# TrainTracker_V01.net
KiCad netlist of a schematic drawn in EAGLE
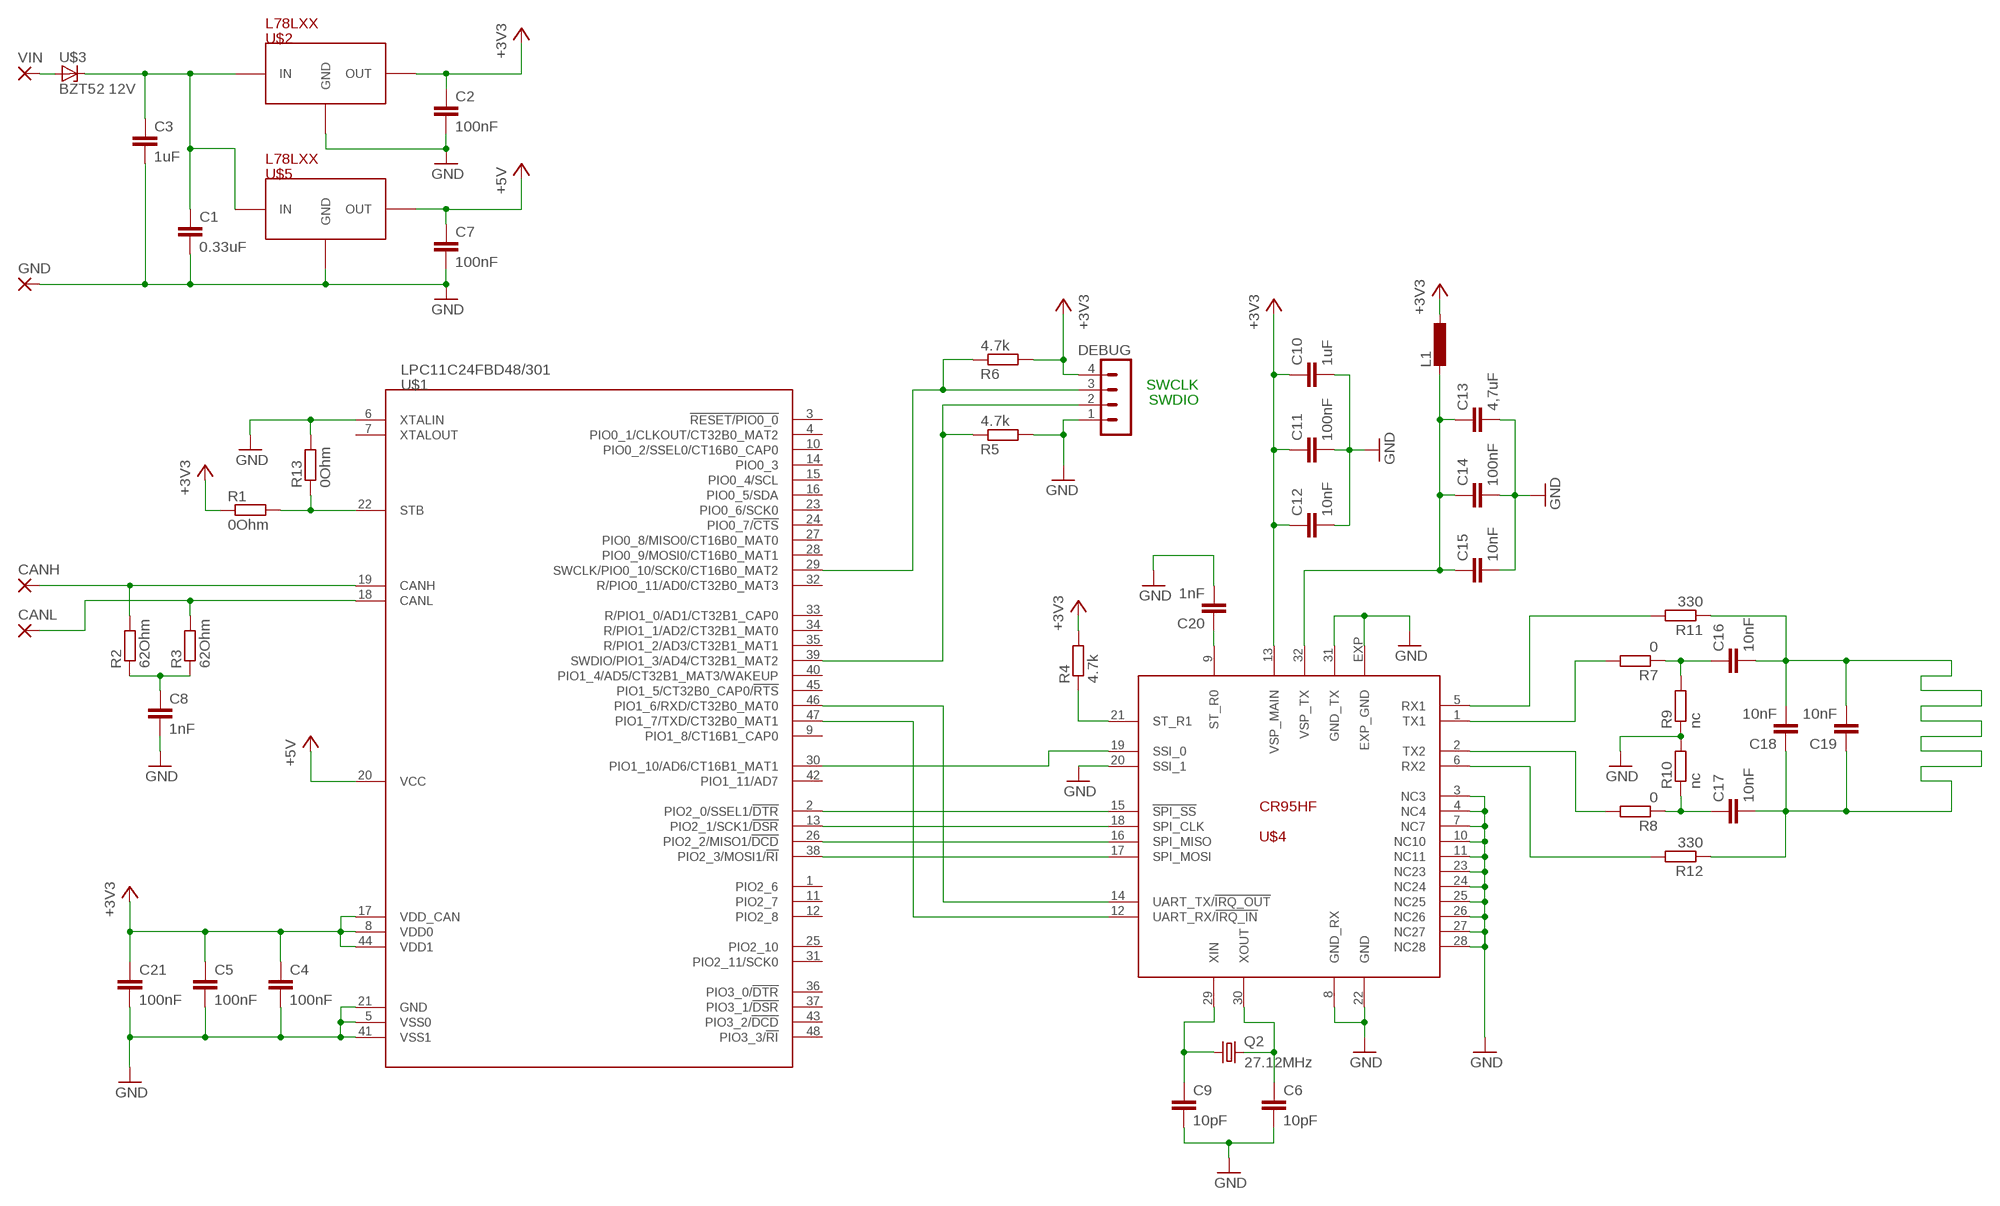
[diagram p0: schematic, sheet 1]

(export (version "E")
  (design (tool "Eeschema 10.0.6"))
  (components
    (comp (ref "C1")
      (value "0.33uF")
      (footprint "eagle-import:C0402")
      (libsource (lib "eagle-import") (part "C-EUC0402"))
    )
    (comp (ref "C2")
      (value "100nF")
      (footprint "eagle-import:C0402")
      (libsource (lib "eagle-import") (part "C-EUC0402"))
    )
    (comp (ref "C3")
      (value "1uF")
      (footprint "eagle-import:C0603K")
      (libsource (lib "eagle-import") (part "C-EUC0603K"))
    )
    (comp (ref "C4")
      (value "100nF")
      (footprint "eagle-import:C0402")
      (libsource (lib "eagle-import") (part "C-EUC0402"))
    )
    (comp (ref "C5")
      (value "100nF")
      (footprint "eagle-import:C0402")
      (libsource (lib "eagle-import") (part "C-EUC0402"))
    )
    (comp (ref "C6")
      (value "10pF")
      (footprint "eagle-import:C0402")
      (libsource (lib "eagle-import") (part "C-EUC0402"))
    )
    (comp (ref "C7")
      (value "100nF")
      (footprint "eagle-import:C0402")
      (libsource (lib "eagle-import") (part "C-EUC0402"))
    )
    (comp (ref "C8")
      (value "1nF")
      (footprint "eagle-import:C0402")
      (libsource (lib "eagle-import") (part "C-EUC0402"))
    )
    (comp (ref "C9")
      (value "10pF")
      (footprint "eagle-import:C0402")
      (libsource (lib "eagle-import") (part "C-EUC0402"))
    )
    (comp (ref "C10")
      (value "1uF")
      (footprint "eagle-import:C0603K")
      (libsource (lib "eagle-import") (part "C-EUC0603K"))
    )
    (comp (ref "C11")
      (value "100nF")
      (footprint "eagle-import:C0402")
      (libsource (lib "eagle-import") (part "C-EUC0402"))
    )
    (comp (ref "C12")
      (value "10nF")
      (footprint "eagle-import:C0402")
      (libsource (lib "eagle-import") (part "C-EUC0402"))
    )
    (comp (ref "C13")
      (value "4,7uF")
      (footprint "eagle-import:C0603K")
      (libsource (lib "eagle-import") (part "C-EUC0603K"))
    )
    (comp (ref "C14")
      (value "100nF")
      (footprint "eagle-import:C0402")
      (libsource (lib "eagle-import") (part "C-EUC0402"))
    )
    (comp (ref "C15")
      (value "10nF")
      (footprint "eagle-import:C0402")
      (libsource (lib "eagle-import") (part "C-EUC0402"))
    )
    (comp (ref "C16")
      (value "10nF")
      (footprint "eagle-import:C0402")
      (libsource (lib "eagle-import") (part "C-EUC0402"))
    )
    (comp (ref "C17")
      (value "10nF")
      (footprint "eagle-import:C0402")
      (libsource (lib "eagle-import") (part "C-EUC0402"))
    )
    (comp (ref "C18")
      (value "10nF")
      (footprint "eagle-import:C0402")
      (libsource (lib "eagle-import") (part "C-EUC0402"))
    )
    (comp (ref "C19")
      (value "10nF")
      (footprint "eagle-import:C0402")
      (libsource (lib "eagle-import") (part "C-EUC0402"))
    )
    (comp (ref "C20")
      (value "1nF")
      (footprint "eagle-import:C0402")
      (libsource (lib "eagle-import") (part "C-EUC0402"))
    )
    (comp (ref "C21")
      (value "100nF")
      (footprint "eagle-import:C0402")
      (libsource (lib "eagle-import") (part "C-EUC0402"))
    )
    (comp (ref "CANH")
      (value "SMD5")
      (footprint "eagle-import:SMD2,54-5,08")
      (libsource (lib "eagle-import") (part "SMD5"))
    )
    (comp (ref "CANL")
      (value "SMD5")
      (footprint "eagle-import:SMD2,54-5,08")
      (libsource (lib "eagle-import") (part "SMD5"))
    )
    (comp (ref "DEBUG")
      (value "MA04-1")
      (footprint "eagle-import:MA04-1")
      (libsource (lib "eagle-import") (part "MA04-1"))
    )
    (comp (ref "GND")
      (value "SMD5")
      (footprint "eagle-import:SMD2,54-5,08")
      (libsource (lib "eagle-import") (part "SMD5"))
    )
    (comp (ref "L1")
      (value "L-EUL3216C")
      (footprint "eagle-import:L3216C")
      (libsource (lib "eagle-import") (part "L-EUL3216C"))
    )
    (comp (ref "Q2")
      (value "27.12MHz")
      (footprint "eagle-import:CTS406")
      (libsource (lib "eagle-import") (part "CRYSTALCTS406"))
    )
    (comp (ref "R1")
      (value "0Ohm")
      (footprint "eagle-import:R0402")
      (libsource (lib "eagle-import") (part "R-EU_R0402"))
    )
    (comp (ref "R2")
      (value "62Ohm")
      (footprint "eagle-import:R0402")
      (libsource (lib "eagle-import") (part "R-EU_R0402"))
    )
    (comp (ref "R3")
      (value "62Ohm")
      (footprint "eagle-import:R0402")
      (libsource (lib "eagle-import") (part "R-EU_R0402"))
    )
    (comp (ref "R4")
      (value "4.7k")
      (footprint "eagle-import:R0402")
      (libsource (lib "eagle-import") (part "R-EU_R0402"))
    )
    (comp (ref "R5")
      (value "4.7k")
      (footprint "eagle-import:R0402")
      (libsource (lib "eagle-import") (part "R-EU_R0402"))
    )
    (comp (ref "R6")
      (value "4.7k")
      (footprint "eagle-import:R0402")
      (libsource (lib "eagle-import") (part "R-EU_R0402"))
    )
    (comp (ref "R7")
      (value "0")
      (footprint "eagle-import:R0402")
      (libsource (lib "eagle-import") (part "R-EU_R0402"))
    )
    (comp (ref "R8")
      (value "0")
      (footprint "eagle-import:R0402")
      (libsource (lib "eagle-import") (part "R-EU_R0402"))
    )
    (comp (ref "R9")
      (value "nc")
      (footprint "eagle-import:R0402")
      (libsource (lib "eagle-import") (part "R-EU_R0402"))
    )
    (comp (ref "R10")
      (value "nc")
      (footprint "eagle-import:R0402")
      (libsource (lib "eagle-import") (part "R-EU_R0402"))
    )
    (comp (ref "R11")
      (value "330")
      (footprint "eagle-import:R0402")
      (libsource (lib "eagle-import") (part "R-EU_R0402"))
    )
    (comp (ref "R12")
      (value "330")
      (footprint "eagle-import:R0402")
      (libsource (lib "eagle-import") (part "R-EU_R0402"))
    )
    (comp (ref "R13")
      (value "0Ohm")
      (footprint "eagle-import:R0402")
      (libsource (lib "eagle-import") (part "R-EU_R0402"))
    )
    (comp (ref "U$1")
      (value "LPC11C24FBD48/301")
      (footprint "eagle-import:LQFP48")
      (libsource (lib "eagle-import") (part "LPC11C24FBD48/301"))
    )
    (comp (ref "U$2")
      (value "L78LXX")
      (footprint "eagle-import:SO8")
      (libsource (lib "eagle-import") (part "L78LXX"))
    )
    (comp (ref "U$3")
      (value "BZT52 12V")
      (footprint "eagle-import:SOD123")
      (libsource (lib "eagle-import") (part "BZT52"))
    )
    (comp (ref "U$4")
      (value "CR95HF")
      (footprint "eagle-import:VFQFPN32")
      (libsource (lib "eagle-import") (part "CR95HF"))
    )
    (comp (ref "U$5")
      (value "L78LXX")
      (footprint "eagle-import:SO8")
      (libsource (lib "eagle-import") (part "L78LXX"))
    )
    (comp (ref "VIN")
      (value "SMD5")
      (footprint "eagle-import:SMD2,54-5,08")
      (libsource (lib "eagle-import") (part "SMD5"))
    )
  )
  (nets
    (net (code "1") (name "+3V3") (class "Default")
      (node (ref "C10") (pin "1") (pinfunction "1_1") (pintype "passive"))
      (node (ref "C11") (pin "1") (pinfunction "1_1") (pintype "passive"))
      (node (ref "C12") (pin "1") (pinfunction "1_1") (pintype "passive"))
      (node (ref "C2") (pin "1") (pinfunction "1_1") (pintype "passive"))
      (node (ref "C21") (pin "1") (pinfunction "1_1") (pintype "passive"))
      (node (ref "C4") (pin "1") (pinfunction "1_1") (pintype "passive"))
      (node (ref "C5") (pin "1") (pinfunction "1_1") (pintype "passive"))
      (node (ref "DEBUG") (pin "4") (pinfunction "4_4") (pintype "passive"))
      (node (ref "L1") (pin "1") (pinfunction "1_1") (pintype "passive"))
      (node (ref "R1") (pin "1") (pinfunction "1_1") (pintype "passive"))
      (node (ref "R4") (pin "2") (pinfunction "2_2") (pintype "passive"))
      (node (ref "R6") (pin "2") (pinfunction "2_2") (pintype "passive"))
      (node (ref "U$1") (pin "17") (pinfunction "VDD_CAN_17") (pintype "bidirectional"))
      (node (ref "U$1") (pin "44") (pinfunction "VDD1_44") (pintype "bidirectional"))
      (node (ref "U$1") (pin "8") (pinfunction "VDD0_8") (pintype "bidirectional"))
      (node (ref "U$2") (pin "1") (pinfunction "OUT_1") (pintype "bidirectional"))
      (node (ref "U$4") (pin "13") (pinfunction "VSP_MAIN_13") (pintype "bidirectional"))
    )
    (net (code "2") (name "+5V") (class "Default")
      (node (ref "C7") (pin "1") (pinfunction "1_1") (pintype "passive"))
      (node (ref "U$1") (pin "20") (pinfunction "VCC_20") (pintype "bidirectional"))
      (node (ref "U$5") (pin "1") (pinfunction "OUT_1") (pintype "bidirectional"))
    )
    (net (code "3") (name "GND") (class "Default")
      (node (ref "C1") (pin "2") (pinfunction "2_2") (pintype "passive"))
      (node (ref "C10") (pin "2") (pinfunction "2_2") (pintype "passive"))
      (node (ref "C11") (pin "2") (pinfunction "2_2") (pintype "passive"))
      (node (ref "C12") (pin "2") (pinfunction "2_2") (pintype "passive"))
      (node (ref "C13") (pin "2") (pinfunction "2_2") (pintype "passive"))
      (node (ref "C14") (pin "2") (pinfunction "2_2") (pintype "passive"))
      (node (ref "C15") (pin "2") (pinfunction "2_2") (pintype "passive"))
      (node (ref "C2") (pin "2") (pinfunction "2_2") (pintype "passive"))
      (node (ref "C20") (pin "2") (pinfunction "2_2") (pintype "passive"))
      (node (ref "C21") (pin "2") (pinfunction "2_2") (pintype "passive"))
      (node (ref "C3") (pin "2") (pinfunction "2_2") (pintype "passive"))
      (node (ref "C4") (pin "2") (pinfunction "2_2") (pintype "passive"))
      (node (ref "C5") (pin "2") (pinfunction "2_2") (pintype "passive"))
      (node (ref "C6") (pin "2") (pinfunction "2_2") (pintype "passive"))
      (node (ref "C7") (pin "2") (pinfunction "2_2") (pintype "passive"))
      (node (ref "C8") (pin "2") (pinfunction "2_2") (pintype "passive"))
      (node (ref "C9") (pin "2") (pinfunction "2_2") (pintype "passive"))
      (node (ref "DEBUG") (pin "1") (pinfunction "1_1") (pintype "passive"))
      (node (ref "GND") (pin "1") (pinfunction "P_1") (pintype "passive"))
      (node (ref "R10") (pin "2") (pinfunction "2_2") (pintype "passive"))
      (node (ref "R13") (pin "2") (pinfunction "2_2") (pintype "passive"))
      (node (ref "R5") (pin "2") (pinfunction "2_2") (pintype "passive"))
      (node (ref "R9") (pin "1") (pinfunction "1_1") (pintype "passive"))
      (node (ref "U$1") (pin "21") (pinfunction "GND_21") (pintype "bidirectional"))
      (node (ref "U$1") (pin "41") (pinfunction "VSS1_41") (pintype "bidirectional"))
      (node (ref "U$1") (pin "5") (pinfunction "VSS0_5") (pintype "bidirectional"))
      (node (ref "U$1") (pin "6") (pinfunction "XTALIN_6") (pintype "bidirectional"))
      (node (ref "U$2") (pin "2") (pinfunction "GND_2") (pintype "bidirectional"))
      (node (ref "U$2") (pin "3") (pinfunction "GND_3") (pintype "bidirectional"))
      (node (ref "U$2") (pin "6") (pinfunction "GND_6") (pintype "bidirectional"))
      (node (ref "U$2") (pin "7") (pinfunction "GND_7") (pintype "bidirectional"))
      (node (ref "U$4") (pin "10") (pinfunction "NC10_10") (pintype "bidirectional"))
      (node (ref "U$4") (pin "11") (pinfunction "NC11_11") (pintype "bidirectional"))
      (node (ref "U$4") (pin "20") (pinfunction "SSI_1_20") (pintype "bidirectional"))
      (node (ref "U$4") (pin "22") (pinfunction "GND_22") (pintype "bidirectional"))
      (node (ref "U$4") (pin "23") (pinfunction "NC23_23") (pintype "bidirectional"))
      (node (ref "U$4") (pin "24") (pinfunction "NC24_24") (pintype "bidirectional"))
      (node (ref "U$4") (pin "25") (pinfunction "NC25_25") (pintype "bidirectional"))
      (node (ref "U$4") (pin "26") (pinfunction "NC26_26") (pintype "bidirectional"))
      (node (ref "U$4") (pin "27") (pinfunction "NC27_27") (pintype "bidirectional"))
      (node (ref "U$4") (pin "28") (pinfunction "NC28_28") (pintype "bidirectional"))
      (node (ref "U$4") (pin "3") (pinfunction "NC3_3") (pintype "bidirectional"))
      (node (ref "U$4") (pin "31") (pinfunction "GND_TX_31") (pintype "bidirectional"))
      (node (ref "U$4") (pin "4") (pinfunction "NC4_4") (pintype "bidirectional"))
      (node (ref "U$4") (pin "7") (pinfunction "NC7_7") (pintype "bidirectional"))
      (node (ref "U$4") (pin "8") (pinfunction "GND_RX_8") (pintype "bidirectional"))
      (node (ref "U$4") (pin "EXP") (pinfunction "EXP_GND_EXP") (pintype "bidirectional"))
      (node (ref "U$5") (pin "2") (pinfunction "GND_2") (pintype "bidirectional"))
      (node (ref "U$5") (pin "3") (pinfunction "GND_3") (pintype "bidirectional"))
      (node (ref "U$5") (pin "6") (pinfunction "GND_6") (pintype "bidirectional"))
      (node (ref "U$5") (pin "7") (pinfunction "GND_7") (pintype "bidirectional"))
    )
    (net (code "4") (name "Net-(C8-Pad1)") (class "Default")
      (node (ref "C8") (pin "1") (pinfunction "1_1") (pintype "passive"))
      (node (ref "R2") (pin "1") (pinfunction "1_1") (pintype "passive"))
      (node (ref "R3") (pin "1") (pinfunction "1_1") (pintype "passive"))
    )
    (net (code "5") (name "Net-(C16-Pad1)") (class "Default")
      (node (ref "C16") (pin "1") (pinfunction "1_1") (pintype "passive"))
      (node (ref "R7") (pin "1") (pinfunction "1_1") (pintype "passive"))
      (node (ref "R9") (pin "2") (pinfunction "2_2") (pintype "passive"))
    )
    (net (code "6") (name "Net-(C16-Pad2)") (class "Default")
      (node (ref "C16") (pin "2") (pinfunction "2_2") (pintype "passive"))
      (node (ref "C17") (pin "2") (pinfunction "2_2") (pintype "passive"))
      (node (ref "C18") (pin "1") (pinfunction "1_1") (pintype "passive"))
      (node (ref "C18") (pin "2") (pinfunction "2_2") (pintype "passive"))
      (node (ref "C19") (pin "1") (pinfunction "1_1") (pintype "passive"))
      (node (ref "C19") (pin "2") (pinfunction "2_2") (pintype "passive"))
      (node (ref "R11") (pin "1") (pinfunction "1_1") (pintype "passive"))
      (node (ref "R12") (pin "1") (pinfunction "1_1") (pintype "passive"))
    )
    (net (code "7") (name "Net-(C17-Pad1)") (class "Default")
      (node (ref "C17") (pin "1") (pinfunction "1_1") (pintype "passive"))
      (node (ref "R10") (pin "1") (pinfunction "1_1") (pintype "passive"))
      (node (ref "R8") (pin "1") (pinfunction "1_1") (pintype "passive"))
    )
    (net (code "8") (name "Net-(CANH-P)") (class "Default")
      (node (ref "CANH") (pin "1") (pinfunction "P_1") (pintype "passive"))
      (node (ref "R2") (pin "2") (pinfunction "2_2") (pintype "passive"))
      (node (ref "U$1") (pin "19") (pinfunction "CANH_19") (pintype "bidirectional"))
    )
    (net (code "9") (name "Net-(CANL-P)") (class "Default")
      (node (ref "CANL") (pin "1") (pinfunction "P_1") (pintype "passive"))
      (node (ref "R3") (pin "2") (pinfunction "2_2") (pintype "passive"))
      (node (ref "U$1") (pin "18") (pinfunction "CANL_18") (pintype "bidirectional"))
    )
    (net (code "10") (name "Net-(Q2-2)") (class "Default")
      (node (ref "C6") (pin "1") (pinfunction "1_1") (pintype "passive"))
      (node (ref "Q2") (pin "3") (pinfunction "2_3") (pintype "passive"))
      (node (ref "U$4") (pin "30") (pinfunction "XOUT_30") (pintype "bidirectional"))
    )
    (net (code "11") (name "Net-(U$1-PIO1_6{slash}RXD{slash}CT32B0_MAT0)") (class "Default")
      (node (ref "U$1") (pin "46") (pinfunction "PIO1_6/RXD/CT32B0_MAT0_46") (pintype "bidirectional"))
      (node (ref "U$4") (pin "14") (pinfunction "UART_TX/~{IRQ_OUT}_14") (pintype "bidirectional"))
    )
    (net (code "12") (name "Net-(U$1-PIO1_7{slash}TXD{slash}CT32B0_MAT1)") (class "Default")
      (node (ref "U$1") (pin "47") (pinfunction "PIO1_7/TXD/CT32B0_MAT1_47") (pintype "bidirectional"))
      (node (ref "U$4") (pin "12") (pinfunction "UART_RX/~{IRQ_IN}_12") (pintype "bidirectional"))
    )
    (net (code "13") (name "Net-(U$1-PIO1_10{slash}AD6{slash}CT16B1_MAT1)") (class "Default")
      (node (ref "U$1") (pin "30") (pinfunction "PIO1_10/AD6/CT16B1_MAT1_30") (pintype "bidirectional"))
      (node (ref "U$4") (pin "19") (pinfunction "SSI_0_19") (pintype "bidirectional"))
    )
    (net (code "14") (name "Net-(U$1-PIO2_0{slash}SSEL1{slash}~{DTR})") (class "Default")
      (node (ref "U$1") (pin "2") (pinfunction "PIO2_0/SSEL1/~{DTR}_2") (pintype "bidirectional"))
      (node (ref "U$4") (pin "15") (pinfunction "~{SPI_SS}_15") (pintype "bidirectional"))
    )
    (net (code "15") (name "Net-(U$1-PIO2_1{slash}SCK1{slash}~{DSR})") (class "Default")
      (node (ref "U$1") (pin "13") (pinfunction "PIO2_1/SCK1/~{DSR}_13") (pintype "bidirectional"))
      (node (ref "U$4") (pin "18") (pinfunction "SPI_CLK_18") (pintype "bidirectional"))
    )
    (net (code "16") (name "Net-(U$1-PIO2_2{slash}MISO1{slash}~{DCD})") (class "Default")
      (node (ref "U$1") (pin "26") (pinfunction "PIO2_2/MISO1/~{DCD}_26") (pintype "bidirectional"))
      (node (ref "U$4") (pin "16") (pinfunction "SPI_MISO_16") (pintype "bidirectional"))
    )
    (net (code "17") (name "Net-(U$1-PIO2_3{slash}MOSI1{slash}~{RI})") (class "Default")
      (node (ref "U$1") (pin "38") (pinfunction "PIO2_3/MOSI1/~{RI}_38") (pintype "bidirectional"))
      (node (ref "U$4") (pin "17") (pinfunction "SPI_MOSI_17") (pintype "bidirectional"))
    )
    (net (code "18") (name "Net-(U$1-STB)") (class "Default")
      (node (ref "R1") (pin "2") (pinfunction "2_2") (pintype "passive"))
      (node (ref "R13") (pin "1") (pinfunction "1_1") (pintype "passive"))
      (node (ref "U$1") (pin "22") (pinfunction "STB_22") (pintype "bidirectional"))
    )
    (net (code "19") (name "Net-(U$1-SWCLK{slash}PIO0_10{slash}SCK0{slash}CT16B0_MAT2)") (class "Default")
      (node (ref "DEBUG") (pin "3") (pinfunction "3_3") (pintype "passive"))
      (node (ref "R6") (pin "1") (pinfunction "1_1") (pintype "passive"))
      (node (ref "U$1") (pin "29") (pinfunction "SWCLK/PIO0_10/SCK0/CT16B0_MAT2_29") (pintype "bidirectional"))
    )
    (net (code "20") (name "Net-(U$1-SWDIO{slash}PIO1_3{slash}AD4{slash}CT32B1_MAT2)") (class "Default")
      (node (ref "DEBUG") (pin "2") (pinfunction "2_2") (pintype "passive"))
      (node (ref "R5") (pin "1") (pinfunction "1_1") (pintype "passive"))
      (node (ref "U$1") (pin "39") (pinfunction "SWDIO/PIO1_3/AD4/CT32B1_MAT2_39") (pintype "bidirectional"))
    )
    (net (code "21") (name "Net-(U$2-IN)") (class "Default")
      (node (ref "C1") (pin "1") (pinfunction "1_1") (pintype "passive"))
      (node (ref "C3") (pin "1") (pinfunction "1_1") (pintype "passive"))
      (node (ref "U$2") (pin "8") (pinfunction "IN_8") (pintype "bidirectional"))
      (node (ref "U$3") (pin "2") (pinfunction "C_2") (pintype "passive"))
      (node (ref "U$5") (pin "8") (pinfunction "IN_8") (pintype "bidirectional"))
    )
    (net (code "22") (name "Net-(U$3-A)") (class "Default")
      (node (ref "U$3") (pin "1") (pinfunction "A_1") (pintype "passive"))
      (node (ref "VIN") (pin "1") (pinfunction "P_1") (pintype "passive"))
    )
    (net (code "23") (name "Net-(U$4-RX1)") (class "Default")
      (node (ref "R11") (pin "2") (pinfunction "2_2") (pintype "passive"))
      (node (ref "U$4") (pin "5") (pinfunction "RX1_5") (pintype "bidirectional"))
    )
    (net (code "24") (name "Net-(U$4-RX2)") (class "Default")
      (node (ref "R12") (pin "2") (pinfunction "2_2") (pintype "passive"))
      (node (ref "U$4") (pin "6") (pinfunction "RX2_6") (pintype "bidirectional"))
    )
    (net (code "25") (name "Net-(U$4-ST_R0)") (class "Default")
      (node (ref "C20") (pin "1") (pinfunction "1_1") (pintype "passive"))
      (node (ref "U$4") (pin "9") (pinfunction "ST_R0_9") (pintype "bidirectional"))
    )
    (net (code "26") (name "Net-(U$4-ST_R1)") (class "Default")
      (node (ref "R4") (pin "1") (pinfunction "1_1") (pintype "passive"))
      (node (ref "U$4") (pin "21") (pinfunction "ST_R1_21") (pintype "bidirectional"))
    )
    (net (code "27") (name "Net-(U$4-TX1)") (class "Default")
      (node (ref "R7") (pin "2") (pinfunction "2_2") (pintype "passive"))
      (node (ref "U$4") (pin "1") (pinfunction "TX1_1") (pintype "bidirectional"))
    )
    (net (code "28") (name "Net-(U$4-TX2)") (class "Default")
      (node (ref "R8") (pin "2") (pinfunction "2_2") (pintype "passive"))
      (node (ref "U$4") (pin "2") (pinfunction "TX2_2") (pintype "bidirectional"))
    )
    (net (code "29") (name "Net-(U$4-VSP_TX)") (class "Default")
      (node (ref "C13") (pin "1") (pinfunction "1_1") (pintype "passive"))
      (node (ref "C14") (pin "1") (pinfunction "1_1") (pintype "passive"))
      (node (ref "C15") (pin "1") (pinfunction "1_1") (pintype "passive"))
      (node (ref "L1") (pin "2") (pinfunction "2_2") (pintype "passive"))
      (node (ref "U$4") (pin "32") (pinfunction "VSP_TX_32") (pintype "bidirectional"))
    )
    (net (code "30") (name "Net-(U$4-XIN)") (class "Default")
      (node (ref "C9") (pin "1") (pinfunction "1_1") (pintype "passive"))
      (node (ref "Q2") (pin "1") (pinfunction "1_1") (pintype "passive"))
      (node (ref "U$4") (pin "29") (pinfunction "XIN_29") (pintype "bidirectional"))
    )
    (net (code "31") (name "unconnected-(U$1-PIO0_1{slash}CLKOUT{slash}CT32B0_MAT2-Pad4)") (class "Default")
      (node (ref "U$1") (pin "4") (pinfunction "PIO0_1/CLKOUT/CT32B0_MAT2_4") (pintype "bidirectional"))
    )
    (net (code "32") (name "unconnected-(U$1-PIO0_2{slash}SSEL0{slash}CT16B0_CAP0-Pad10)") (class "Default")
      (node (ref "U$1") (pin "10") (pinfunction "PIO0_2/SSEL0/CT16B0_CAP0_10") (pintype "bidirectional"))
    )
    (net (code "33") (name "unconnected-(U$1-PIO0_3-Pad14)") (class "Default")
      (node (ref "U$1") (pin "14") (pinfunction "PIO0_3_14") (pintype "bidirectional"))
    )
    (net (code "34") (name "unconnected-(U$1-PIO0_4{slash}SCL-Pad15)") (class "Default")
      (node (ref "U$1") (pin "15") (pinfunction "PIO0_4/SCL_15") (pintype "bidirectional"))
    )
    (net (code "35") (name "unconnected-(U$1-PIO0_5{slash}SDA-Pad16)") (class "Default")
      (node (ref "U$1") (pin "16") (pinfunction "PIO0_5/SDA_16") (pintype "bidirectional"))
    )
    (net (code "36") (name "unconnected-(U$1-PIO0_6{slash}SCK0-Pad23)") (class "Default")
      (node (ref "U$1") (pin "23") (pinfunction "PIO0_6/SCK0_23") (pintype "bidirectional"))
    )
    (net (code "37") (name "unconnected-(U$1-PIO0_7{slash}~{CTS}-Pad24)") (class "Default")
      (node (ref "U$1") (pin "24") (pinfunction "PIO0_7/~{CTS}_24") (pintype "bidirectional"))
    )
    (net (code "38") (name "unconnected-(U$1-PIO0_8{slash}MISO0{slash}CT16B0_MAT0-Pad27)") (class "Default")
      (node (ref "U$1") (pin "27") (pinfunction "PIO0_8/MISO0/CT16B0_MAT0_27") (pintype "bidirectional"))
    )
    (net (code "39") (name "unconnected-(U$1-PIO0_9{slash}MOSI0{slash}CT16B0_MAT1-Pad28)") (class "Default")
      (node (ref "U$1") (pin "28") (pinfunction "PIO0_9/MOSI0/CT16B0_MAT1_28") (pintype "bidirectional"))
    )
    (net (code "40") (name "unconnected-(U$1-PIO1_4{slash}AD5{slash}CT32B1_MAT3{slash}WAKEUP-Pad40)") (class "Default")
      (node (ref "U$1") (pin "40") (pinfunction "PIO1_4/AD5/CT32B1_MAT3/WAKEUP_40") (pintype "bidirectional"))
    )
    (net (code "41") (name "unconnected-(U$1-PIO1_5{slash}CT32B0_CAP0{slash}~{RTS}-Pad45)") (class "Default")
      (node (ref "U$1") (pin "45") (pinfunction "PIO1_5/CT32B0_CAP0/~{RTS}_45") (pintype "bidirectional"))
    )
    (net (code "42") (name "unconnected-(U$1-PIO1_8{slash}CT16B1_CAP0-Pad9)") (class "Default")
      (node (ref "U$1") (pin "9") (pinfunction "PIO1_8/CT16B1_CAP0_9") (pintype "bidirectional"))
    )
    (net (code "43") (name "unconnected-(U$1-PIO1_11{slash}AD7-Pad42)") (class "Default")
      (node (ref "U$1") (pin "42") (pinfunction "PIO1_11/AD7_42") (pintype "bidirectional"))
    )
    (net (code "44") (name "unconnected-(U$1-PIO2_6-Pad1)") (class "Default")
      (node (ref "U$1") (pin "1") (pinfunction "PIO2_6_1") (pintype "bidirectional"))
    )
    (net (code "45") (name "unconnected-(U$1-PIO2_7-Pad11)") (class "Default")
      (node (ref "U$1") (pin "11") (pinfunction "PIO2_7_11") (pintype "bidirectional"))
    )
    (net (code "46") (name "unconnected-(U$1-PIO2_8-Pad12)") (class "Default")
      (node (ref "U$1") (pin "12") (pinfunction "PIO2_8_12") (pintype "bidirectional"))
    )
    (net (code "47") (name "unconnected-(U$1-PIO2_10-Pad25)") (class "Default")
      (node (ref "U$1") (pin "25") (pinfunction "PIO2_10_25") (pintype "bidirectional"))
    )
    (net (code "48") (name "unconnected-(U$1-PIO2_11{slash}SCK0-Pad31)") (class "Default")
      (node (ref "U$1") (pin "31") (pinfunction "PIO2_11/SCK0_31") (pintype "bidirectional"))
    )
    (net (code "49") (name "unconnected-(U$1-PIO3_0{slash}~{DTR}-Pad36)") (class "Default")
      (node (ref "U$1") (pin "36") (pinfunction "PIO3_0/~{DTR}_36") (pintype "bidirectional"))
    )
    (net (code "50") (name "unconnected-(U$1-PIO3_1{slash}~{DSR}-Pad37)") (class "Default")
      (node (ref "U$1") (pin "37") (pinfunction "PIO3_1/~{DSR}_37") (pintype "bidirectional"))
    )
    (net (code "51") (name "unconnected-(U$1-PIO3_2{slash}~{DCD}-Pad43)") (class "Default")
      (node (ref "U$1") (pin "43") (pinfunction "PIO3_2/~{DCD}_43") (pintype "bidirectional"))
    )
    (net (code "52") (name "unconnected-(U$1-PIO3_3{slash}~{RI}-Pad48)") (class "Default")
      (node (ref "U$1") (pin "48") (pinfunction "PIO3_3/~{RI}_48") (pintype "bidirectional"))
    )
    (net (code "53") (name "unconnected-(U$1-R{slash}PIO0_11{slash}AD0{slash}CT32B0_MAT3-Pad32)") (class "Default")
      (node (ref "U$1") (pin "32") (pinfunction "R/PIO0_11/AD0/CT32B0_MAT3_32") (pintype "bidirectional"))
    )
    (net (code "54") (name "unconnected-(U$1-R{slash}PIO1_0{slash}AD1{slash}CT32B1_CAP0-Pad33)") (class "Default")
      (node (ref "U$1") (pin "33") (pinfunction "R/PIO1_0/AD1/CT32B1_CAP0_33") (pintype "bidirectional"))
    )
    (net (code "55") (name "unconnected-(U$1-R{slash}PIO1_1{slash}AD2{slash}CT32B1_MAT0-Pad34)") (class "Default")
      (node (ref "U$1") (pin "34") (pinfunction "R/PIO1_1/AD2/CT32B1_MAT0_34") (pintype "bidirectional"))
    )
    (net (code "56") (name "unconnected-(U$1-R{slash}PIO1_2{slash}AD3{slash}CT32B1_MAT1-Pad35)") (class "Default")
      (node (ref "U$1") (pin "35") (pinfunction "R/PIO1_2/AD3/CT32B1_MAT1_35") (pintype "bidirectional"))
    )
    (net (code "57") (name "unconnected-(U$1-XTALOUT-Pad7)") (class "Default")
      (node (ref "U$1") (pin "7") (pinfunction "XTALOUT_7") (pintype "bidirectional"))
    )
    (net (code "58") (name "unconnected-(U$1-~{RESET{slash}PIO0_0}-Pad3)") (class "Default")
      (node (ref "U$1") (pin "3") (pinfunction "~{RESET/PIO0_0}_3") (pintype "bidirectional"))
    )
  )
)
